# Lower.net
KiCad netlist of a schematic drawn in Altium Designer
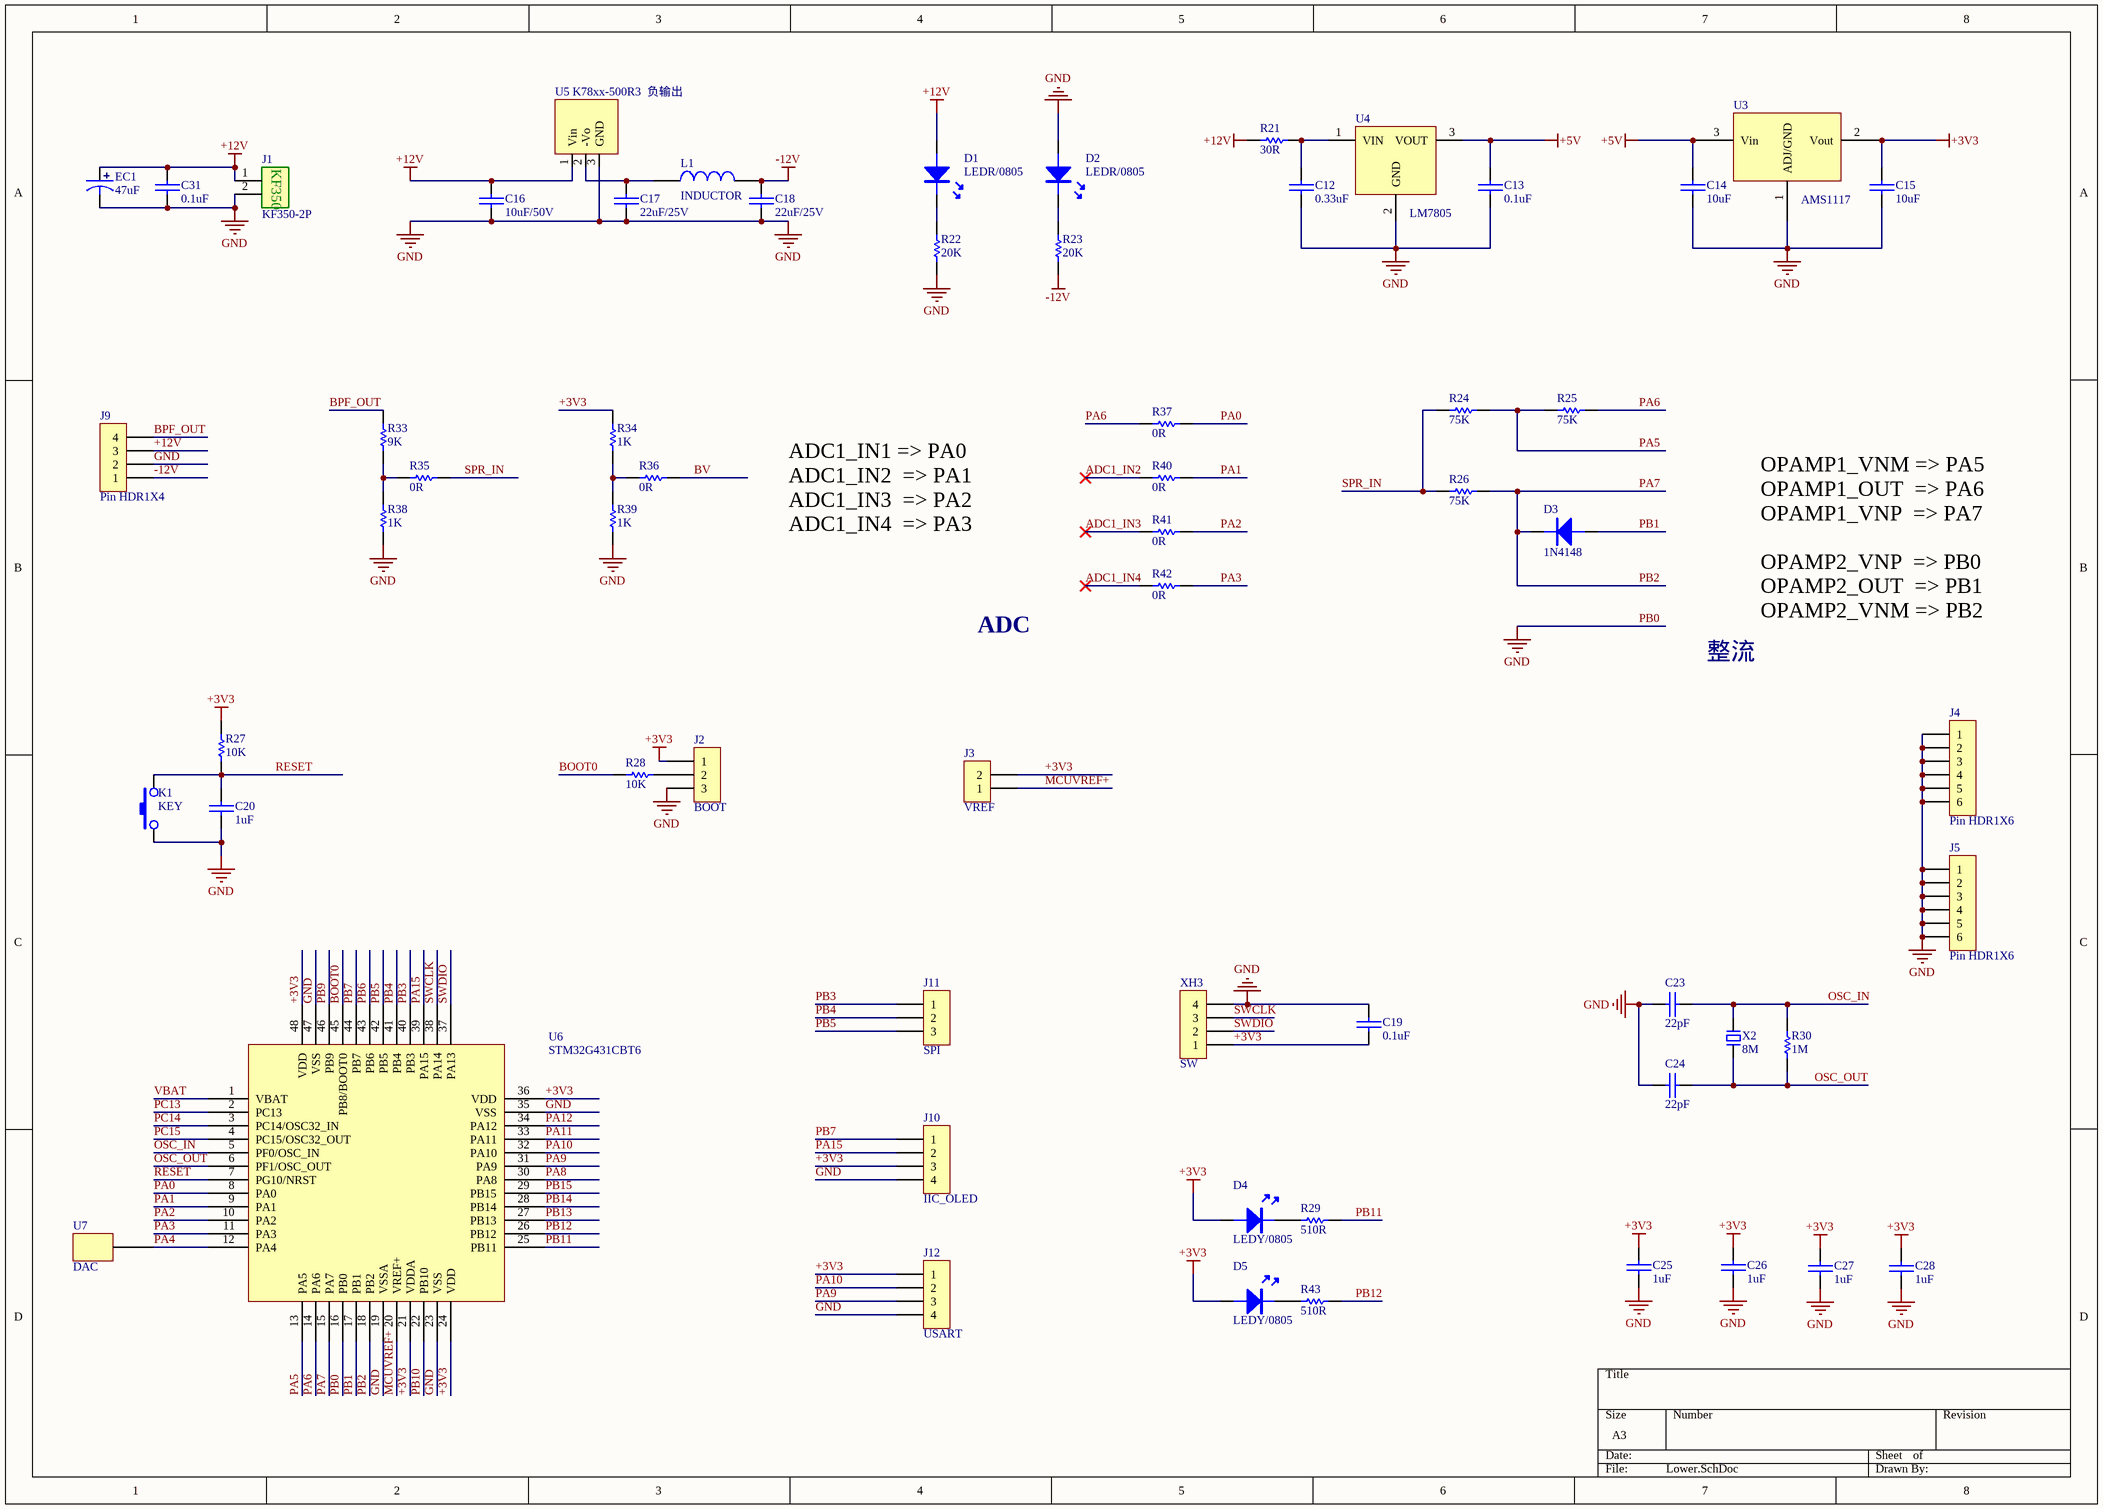
[diagram p0: Lower.SchDoc]

(export (version "E")
  (design (tool "Eeschema 10.0.6"))
  (components
    (comp (ref "C12")
      (value "0.33uF")
      (footprint "0603C")
      (description "无极性电容")
      (libsource (lib "电容") (part "CAP"))
    )
    (comp (ref "C13")
      (value "0.1uF")
      (footprint "0603C")
      (description "无极性电容")
      (libsource (lib "电容") (part "CAP"))
    )
    (comp (ref "C14")
      (value "10uF")
      (footprint "0603C")
      (description "无极性电容")
      (libsource (lib "电容") (part "CAP"))
    )
    (comp (ref "C15")
      (value "10uF")
      (footprint "0603C")
      (description "无极性电容")
      (libsource (lib "电容") (part "CAP"))
    )
    (comp (ref "C16")
      (value "10uF/50V")
      (footprint "0603C")
      (description "无极性电容")
      (libsource (lib "电容") (part "CAP"))
    )
    (comp (ref "C17")
      (value "22uF/25V")
      (footprint "0603C")
      (description "无极性电容")
      (libsource (lib "电容") (part "CAP"))
    )
    (comp (ref "C18")
      (value "22uF/25V")
      (footprint "0603C")
      (description "无极性电容")
      (libsource (lib "电容") (part "CAP"))
    )
    (comp (ref "C19")
      (value "0.1uF")
      (footprint "0603C")
      (description "无极性电容")
      (libsource (lib "电容") (part "CAP"))
    )
    (comp (ref "C20")
      (value "1uF")
      (footprint "0603C")
      (description "无极性电容")
      (libsource (lib "电容") (part "CAP"))
    )
    (comp (ref "C23")
      (value "22pF")
      (footprint "0603C")
      (description "无极性电容")
      (libsource (lib "电容") (part "CAP"))
    )
    (comp (ref "C24")
      (value "22pF")
      (footprint "0603C")
      (description "无极性电容")
      (libsource (lib "电容") (part "CAP"))
    )
    (comp (ref "C25")
      (value "1uF")
      (footprint "0603C")
      (description "无极性电容")
      (libsource (lib "电容") (part "CAP"))
    )
    (comp (ref "C26")
      (value "1uF")
      (footprint "0603C")
      (description "无极性电容")
      (libsource (lib "电容") (part "CAP"))
    )
    (comp (ref "C27")
      (value "1uF")
      (footprint "0603C")
      (description "无极性电容")
      (libsource (lib "电容") (part "CAP"))
    )
    (comp (ref "C28")
      (value "1uF")
      (footprint "0603C")
      (description "无极性电容")
      (libsource (lib "电容") (part "CAP"))
    )
    (comp (ref "C31")
      (value "0.1uF")
      (footprint "0603C")
      (description "无极性电容")
      (libsource (lib "电容") (part "CAP"))
    )
    (comp (ref "D1") (value "LEDR/0805") (footprint "LED-0805R") (libsource (lib "LED") (part "LED")))
    (comp (ref "D2") (value "LEDR/0805") (footprint "LED-0805R") (libsource (lib "LED") (part "LED")))
    (comp (ref "D3")
      (value "1N4148")
      (footprint "SOD-123")
      (description "普通二极管")
      (libsource (lib "二极管") (part "DIODE"))
    )
    (comp (ref "D4") (value "LEDY/0805") (footprint "LED-0805B") (libsource (lib "LED") (part "LED")))
    (comp (ref "D5") (value "LEDY/0805") (footprint "LED-0805G") (libsource (lib "LED") (part "LED")))
    (comp (ref "EC1")
      (value "47uF")
      (footprint "SMD-EC5.0X5.3X5.4")
      (description "贴片电解电容")
      (libsource (lib "电容") (part "SMD_ECAP"))
    )
    (comp (ref "J1") (value "KF350-2P") (footprint "KF350-2P") (libsource (lib "KF350") (part "KF350-2P")))
    (comp (ref "J2")
      (value "BOOT")
      (footprint "Pin HDR1X3/2.54mm-S")
      (libsource (lib "排针") (part "Pin HDR1X3"))
    )
    (comp (ref "J3")
      (value "VREF")
      (footprint "Pin HDR1X2/2.54mm-S")
      (libsource (lib "排针") (part "Pin HDR1X2"))
    )
    (comp (ref "J4")
      (value "Pin HDR1X6")
      (footprint "Pin HDR1X6/2.54mm-S")
      (libsource (lib "排针") (part "Pin HDR1X6"))
    )
    (comp (ref "J5")
      (value "Pin HDR1X6")
      (footprint "Pin HDR1X6/2.54mm-S")
      (libsource (lib "排针") (part "Pin HDR1X6"))
    )
    (comp (ref "J9")
      (value "Pin HDR1X4")
      (footprint "Pin HDR1X4/2.54mm-S")
      (libsource (lib "排针") (part "Pin HDR1X4"))
    )
    (comp (ref "J10")
      (value "IIC_OLED")
      (footprint "Fe-HDR1X4/2.54-S")
      (libsource (lib "排母") (part "Female HDR1X4"))
    )
    (comp (ref "J11")
      (value "SPI")
      (footprint "Pin HDR1X3/2.54mm-S")
      (libsource (lib "排针") (part "Pin HDR1X3"))
    )
    (comp (ref "J12")
      (value "USART")
      (footprint "Fe-HDR1X4/2.54-S")
      (libsource (lib "排母") (part "Female HDR1X4"))
    )
    (comp (ref "K1") (value "KEY") (footprint "SMD-3X6X2.5") (libsource (lib "轻触开关") (part "KEY")))
    (comp (ref "L1") (value "INDUCTOR") (footprint "1210L") (libsource (lib "电感") (part "INDUCTOR")))
    (comp (ref "R21") (value "30R") (footprint "0603R") (libsource (lib "电阻") (part "RES")))
    (comp (ref "R22") (value "20K") (footprint "0603R") (libsource (lib "电阻") (part "RES")))
    (comp (ref "R23") (value "20K") (footprint "0603R") (libsource (lib "电阻") (part "RES")))
    (comp (ref "R24") (value "75K") (footprint "0603R") (libsource (lib "电阻") (part "RES")))
    (comp (ref "R25") (value "75K") (footprint "0603R") (libsource (lib "电阻") (part "RES")))
    (comp (ref "R26") (value "75K") (footprint "0603R") (libsource (lib "电阻") (part "RES")))
    (comp (ref "R27") (value "10K") (footprint "0603R") (libsource (lib "电阻") (part "RES")))
    (comp (ref "R28") (value "10K") (footprint "0603R") (libsource (lib "电阻") (part "RES")))
    (comp (ref "R29") (value "510R") (footprint "0603R") (libsource (lib "电阻") (part "RES")))
    (comp (ref "R30") (value "1M") (footprint "0603R") (libsource (lib "电阻") (part "RES")))
    (comp (ref "R33") (value "9K") (footprint "0603R") (libsource (lib "电阻") (part "RES")))
    (comp (ref "R34") (value "1K") (footprint "0603R") (libsource (lib "电阻") (part "RES")))
    (comp (ref "R35") (value "0R") (footprint "0603R") (libsource (lib "电阻") (part "RES")))
    (comp (ref "R36") (value "0R") (footprint "0603R") (libsource (lib "电阻") (part "RES")))
    (comp (ref "R37") (value "0R") (footprint "0603R") (libsource (lib "电阻") (part "RES")))
    (comp (ref "R38") (value "1K") (footprint "0603R") (libsource (lib "电阻") (part "RES")))
    (comp (ref "R39") (value "1K") (footprint "0603R") (libsource (lib "电阻") (part "RES")))
    (comp (ref "R40") (value "0R") (footprint "0603R") (libsource (lib "电阻") (part "RES")))
    (comp (ref "R41") (value "0R") (footprint "0603R") (libsource (lib "电阻") (part "RES")))
    (comp (ref "R42") (value "0R") (footprint "0603R") (libsource (lib "电阻") (part "RES")))
    (comp (ref "R43") (value "510R") (footprint "0603R") (libsource (lib "电阻") (part "RES")))
    (comp (ref "U3")
      (value "AMS1117")
      (footprint "SOT223")
      (description "三端稳压芯片")
      (libsource (lib "电源芯片") (part "AMS1117"))
    )
    (comp (ref "U4") (value "LM7805") (footprint "TO252") (libsource (lib "电源芯片") (part "LM7805")))
    (comp (ref "U5")
      (value "K78xx-500R3  负输出")
      (footprint "K78xx-500R3 负输出")
      (libsource (lib "传感器") (part "K78xx-500R3  负输出"))
    )
    (comp (ref "U6")
      (value "STM32G431CBT6")
      (footprint "LQFP48 7X7")
      (libsource (lib "STM32系列") (part "STM32G431CBT6"))
    )
    (comp (ref "U7") (value "DAC") (footprint "通孔焊盘") (libsource (lib "排母") (part "过孔焊盘")))
    (comp (ref "X2")
      (value "8M")
      (footprint "OSC HC-49S")
      (description "2脚无源脚晶振")
      (libsource (lib "晶振") (part "XTAL-2P"))
    )
    (comp (ref "XH3") (value "SW") (footprint "XH4/2.54mm/90") (libsource (lib "XH，VH") (part "XH4")))
  )
  (nets
    (net (code "1") (name "+3V3") (class "Default")
      (node (ref "C15") (pin "2") (pinfunction "2_2") (pintype "passive"))
      (node (ref "C19") (pin "1") (pinfunction "1_1") (pintype "passive"))
      (node (ref "C25") (pin "2") (pinfunction "2_2") (pintype "passive"))
      (node (ref "C26") (pin "2") (pinfunction "2_2") (pintype "passive"))
      (node (ref "C27") (pin "2") (pinfunction "2_2") (pintype "passive"))
      (node (ref "C28") (pin "2") (pinfunction "2_2") (pintype "passive"))
      (node (ref "D4") (pin "A") (pinfunction "A_A") (pintype "passive"))
      (node (ref "D5") (pin "A") (pinfunction "A_A") (pintype "passive"))
      (node (ref "J10") (pin "3") (pinfunction "3_3") (pintype "passive"))
      (node (ref "J12") (pin "1") (pinfunction "1_1") (pintype "passive"))
      (node (ref "J2") (pin "1") (pinfunction "1_1") (pintype "passive"))
      (node (ref "J3") (pin "2") (pinfunction "2_2") (pintype "passive"))
      (node (ref "R27") (pin "1") (pinfunction "1_1") (pintype "passive"))
      (node (ref "R34") (pin "2") (pinfunction "2_2") (pintype "passive"))
      (node (ref "U3") (pin "2") (pinfunction "Vout_2") (pintype "passive"))
      (node (ref "U6") (pin "21") (pinfunction "VDDA_21") (pintype "passive"))
      (node (ref "U6") (pin "24") (pinfunction "VDD_24") (pintype "passive"))
      (node (ref "U6") (pin "36") (pinfunction "VDD_36") (pintype "passive"))
      (node (ref "U6") (pin "48") (pinfunction "VDD_48") (pintype "passive"))
      (node (ref "XH3") (pin "1") (pinfunction "1_1") (pintype "passive"))
    )
    (net (code "2") (name "+5V") (class "Default")
      (node (ref "C13") (pin "2") (pinfunction "2_2") (pintype "passive"))
      (node (ref "C14") (pin "2") (pinfunction "2_2") (pintype "passive"))
      (node (ref "U3") (pin "3") (pinfunction "Vin_3") (pintype "passive"))
      (node (ref "U4") (pin "3") (pinfunction "VOUT_3") (pintype "passive"))
    )
    (net (code "3") (name "+12V") (class "Default")
      (node (ref "C16") (pin "2") (pinfunction "2_2") (pintype "passive"))
      (node (ref "C31") (pin "2") (pinfunction "2_2") (pintype "passive"))
      (node (ref "D1") (pin "A") (pinfunction "A_A") (pintype "passive"))
      (node (ref "EC1") (pin "1") (pinfunction "1_1") (pintype "passive"))
      (node (ref "J1") (pin "1") (pinfunction "1_1") (pintype "passive"))
      (node (ref "J9") (pin "3") (pinfunction "3_3") (pintype "passive"))
      (node (ref "R21") (pin "1") (pinfunction "1_1") (pintype "passive"))
      (node (ref "U5") (pin "1") (pinfunction "Vin_1") (pintype "passive"))
    )
    (net (code "4") (name "-12V") (class "Default")
      (node (ref "C18") (pin "2") (pinfunction "2_2") (pintype "passive"))
      (node (ref "J9") (pin "1") (pinfunction "1_1") (pintype "passive"))
      (node (ref "L1") (pin "2") (pinfunction "2_2") (pintype "passive"))
      (node (ref "R23") (pin "2") (pinfunction "2_2") (pintype "passive"))
    )
    (net (code "5") (name "/ADC1_IN2") (class "Default")
      (node (ref "R40") (pin "1") (pinfunction "1_1") (pintype "passive+no_connect"))
    )
    (net (code "6") (name "/ADC1_IN3") (class "Default")
      (node (ref "R41") (pin "1") (pinfunction "1_1") (pintype "passive+no_connect"))
    )
    (net (code "7") (name "/ADC1_IN4") (class "Default")
      (node (ref "R42") (pin "1") (pinfunction "1_1") (pintype "passive+no_connect"))
    )
    (net (code "8") (name "/BOOT0") (class "Default")
      (node (ref "R28") (pin "1") (pinfunction "1_1") (pintype "passive"))
      (node (ref "U6") (pin "45") (pinfunction "PB8/BOOT0_45") (pintype "passive"))
    )
    (net (code "9") (name "/BPF_OUT") (class "Default")
      (node (ref "J9") (pin "4") (pinfunction "4_4") (pintype "passive"))
      (node (ref "R33") (pin "2") (pinfunction "2_2") (pintype "passive"))
    )
    (net (code "10") (name "/BV") (class "Default")
      (node (ref "R36") (pin "1") (pinfunction "1_1") (pintype "passive"))
    )
    (net (code "11") (name "/MCUVREF+") (class "Default")
      (node (ref "J3") (pin "1") (pinfunction "1_1") (pintype "passive"))
      (node (ref "U6") (pin "20") (pinfunction "VREF+_20") (pintype "passive"))
    )
    (net (code "12") (name "/OSC_IN") (class "Default")
      (node (ref "C23") (pin "1") (pinfunction "1_1") (pintype "passive"))
      (node (ref "R30") (pin "2") (pinfunction "2_2") (pintype "passive"))
      (node (ref "U6") (pin "5") (pinfunction "PF0/OSC_IN_5") (pintype "passive"))
      (node (ref "X2") (pin "2") (pinfunction "2_2") (pintype "passive"))
    )
    (net (code "13") (name "/OSC_OUT") (class "Default")
      (node (ref "C24") (pin "1") (pinfunction "1_1") (pintype "passive"))
      (node (ref "R30") (pin "1") (pinfunction "1_1") (pintype "passive"))
      (node (ref "U6") (pin "6") (pinfunction "PF1/OSC_OUT_6") (pintype "passive"))
      (node (ref "X2") (pin "1") (pinfunction "1_1") (pintype "passive"))
    )
    (net (code "14") (name "/PA0") (class "Default")
      (node (ref "R37") (pin "2") (pinfunction "2_2") (pintype "passive"))
      (node (ref "U6") (pin "8") (pinfunction "PA0_8") (pintype "passive"))
    )
    (net (code "15") (name "/PA1") (class "Default")
      (node (ref "R40") (pin "2") (pinfunction "2_2") (pintype "passive"))
      (node (ref "U6") (pin "9") (pinfunction "PA1_9") (pintype "passive"))
    )
    (net (code "16") (name "/PA2") (class "Default")
      (node (ref "R41") (pin "2") (pinfunction "2_2") (pintype "passive"))
      (node (ref "U6") (pin "10") (pinfunction "PA2_10") (pintype "passive"))
    )
    (net (code "17") (name "/PA3") (class "Default")
      (node (ref "R42") (pin "2") (pinfunction "2_2") (pintype "passive"))
      (node (ref "U6") (pin "11") (pinfunction "PA3_11") (pintype "passive"))
    )
    (net (code "18") (name "/PA4") (class "Default")
      (node (ref "U6") (pin "12") (pinfunction "PA4_12") (pintype "passive"))
      (node (ref "U7") (pin "Hole") (pinfunction "Con_Hole") (pintype "passive"))
    )
    (net (code "19") (name "/PA5") (class "Default")
      (node (ref "R24") (pin "2") (pinfunction "2_2") (pintype "passive"))
      (node (ref "R25") (pin "1") (pinfunction "1_1") (pintype "passive"))
      (node (ref "U6") (pin "13") (pinfunction "PA5_13") (pintype "passive"))
    )
    (net (code "20") (name "/PA6") (class "Default")
      (node (ref "R25") (pin "2") (pinfunction "2_2") (pintype "passive"))
      (node (ref "R37") (pin "1") (pinfunction "1_1") (pintype "passive"))
      (node (ref "U6") (pin "14") (pinfunction "PA6_14") (pintype "passive"))
    )
    (net (code "21") (name "/PA7") (class "Default")
      (node (ref "D3") (pin "K") (pinfunction "K_K") (pintype "passive"))
      (node (ref "R26") (pin "2") (pinfunction "2_2") (pintype "passive"))
      (node (ref "U6") (pin "15") (pinfunction "PA7_15") (pintype "passive"))
      (node (ref "U6") (pin "18") (pinfunction "PB2_18") (pintype "passive"))
    )
    (net (code "22") (name "/PA8") (class "Default")
      (node (ref "U6") (pin "30") (pinfunction "PA8_30") (pintype "passive"))
    )
    (net (code "23") (name "/PA9") (class "Default")
      (node (ref "J12") (pin "3") (pinfunction "3_3") (pintype "passive"))
      (node (ref "U6") (pin "31") (pinfunction "PA9_31") (pintype "passive"))
    )
    (net (code "24") (name "/PA10") (class "Default")
      (node (ref "J12") (pin "2") (pinfunction "2_2") (pintype "passive"))
      (node (ref "U6") (pin "32") (pinfunction "PA10_32") (pintype "passive"))
    )
    (net (code "25") (name "/PA11") (class "Default")
      (node (ref "U6") (pin "33") (pinfunction "PA11_33") (pintype "passive"))
    )
    (net (code "26") (name "/PA12") (class "Default")
      (node (ref "U6") (pin "34") (pinfunction "PA12_34") (pintype "passive"))
    )
    (net (code "27") (name "/PA15") (class "Default")
      (node (ref "J10") (pin "2") (pinfunction "2_2") (pintype "passive"))
      (node (ref "U6") (pin "39") (pinfunction "PA15_39") (pintype "passive"))
    )
    (net (code "28") (name "/PB1") (class "Default")
      (node (ref "D3") (pin "A") (pinfunction "A_A") (pintype "passive"))
      (node (ref "U6") (pin "17") (pinfunction "PB1_17") (pintype "passive"))
    )
    (net (code "29") (name "/PB3") (class "Default")
      (node (ref "J11") (pin "1") (pinfunction "1_1") (pintype "passive"))
      (node (ref "U6") (pin "40") (pinfunction "PB3_40") (pintype "passive"))
    )
    (net (code "30") (name "/PB4") (class "Default")
      (node (ref "J11") (pin "2") (pinfunction "2_2") (pintype "passive"))
      (node (ref "U6") (pin "41") (pinfunction "PB4_41") (pintype "passive"))
    )
    (net (code "31") (name "/PB5") (class "Default")
      (node (ref "J11") (pin "3") (pinfunction "3_3") (pintype "passive"))
      (node (ref "U6") (pin "42") (pinfunction "PB5_42") (pintype "passive"))
    )
    (net (code "32") (name "/PB6") (class "Default")
      (node (ref "U6") (pin "43") (pinfunction "PB6_43") (pintype "passive"))
    )
    (net (code "33") (name "/PB7") (class "Default")
      (node (ref "J10") (pin "1") (pinfunction "1_1") (pintype "passive"))
      (node (ref "U6") (pin "44") (pinfunction "PB7_44") (pintype "passive"))
    )
    (net (code "34") (name "/PB9") (class "Default")
      (node (ref "U6") (pin "46") (pinfunction "PB9_46") (pintype "passive"))
    )
    (net (code "35") (name "/PB10") (class "Default")
      (node (ref "U6") (pin "22") (pinfunction "PB10_22") (pintype "passive"))
    )
    (net (code "36") (name "/PB11") (class "Default")
      (node (ref "R29") (pin "2") (pinfunction "2_2") (pintype "passive"))
      (node (ref "U6") (pin "25") (pinfunction "PB11_25") (pintype "passive"))
    )
    (net (code "37") (name "/PB12") (class "Default")
      (node (ref "R43") (pin "2") (pinfunction "2_2") (pintype "passive"))
      (node (ref "U6") (pin "26") (pinfunction "PB12_26") (pintype "passive"))
    )
    (net (code "38") (name "/PB13") (class "Default")
      (node (ref "U6") (pin "27") (pinfunction "PB13_27") (pintype "passive"))
    )
    (net (code "39") (name "/PB14") (class "Default")
      (node (ref "U6") (pin "28") (pinfunction "PB14_28") (pintype "passive"))
    )
    (net (code "40") (name "/PB15") (class "Default")
      (node (ref "U6") (pin "29") (pinfunction "PB15_29") (pintype "passive"))
    )
    (net (code "41") (name "/PC13") (class "Default")
      (node (ref "U6") (pin "2") (pinfunction "PC13_2") (pintype "passive"))
    )
    (net (code "42") (name "/PC14") (class "Default")
      (node (ref "U6") (pin "3") (pinfunction "PC14/OSC32_IN_3") (pintype "passive"))
    )
    (net (code "43") (name "/PC15") (class "Default")
      (node (ref "U6") (pin "4") (pinfunction "PC15/OSC32_OUT_4") (pintype "passive"))
    )
    (net (code "44") (name "/RESET") (class "Default")
      (node (ref "C20") (pin "2") (pinfunction "2_2") (pintype "passive"))
      (node (ref "K1") (pin "3") (pinfunction "3_3") (pintype "passive"))
      (node (ref "R27") (pin "2") (pinfunction "2_2") (pintype "passive"))
      (node (ref "U6") (pin "7") (pinfunction "PG10/NRST_7") (pintype "passive"))
    )
    (net (code "45") (name "/SPR_IN") (class "Default")
      (node (ref "R24") (pin "1") (pinfunction "1_1") (pintype "passive"))
      (node (ref "R26") (pin "1") (pinfunction "1_1") (pintype "passive"))
      (node (ref "R35") (pin "1") (pinfunction "1_1") (pintype "passive"))
    )
    (net (code "46") (name "/SWCLK") (class "Default")
      (node (ref "U6") (pin "38") (pinfunction "PA14_38") (pintype "passive"))
      (node (ref "XH3") (pin "3") (pinfunction "3_3") (pintype "passive"))
    )
    (net (code "47") (name "/SWDIO") (class "Default")
      (node (ref "U6") (pin "37") (pinfunction "PA13_37") (pintype "passive"))
      (node (ref "XH3") (pin "2") (pinfunction "2_2") (pintype "passive"))
    )
    (net (code "48") (name "/VBAT") (class "Default")
      (node (ref "U6") (pin "1") (pinfunction "VBAT_1") (pintype "passive"))
    )
    (net (code "49") (name "GND") (class "Default")
      (node (ref "C12") (pin "1") (pinfunction "1_1") (pintype "passive"))
      (node (ref "C13") (pin "1") (pinfunction "1_1") (pintype "passive"))
      (node (ref "C14") (pin "1") (pinfunction "1_1") (pintype "passive"))
      (node (ref "C15") (pin "1") (pinfunction "1_1") (pintype "passive"))
      (node (ref "C16") (pin "1") (pinfunction "1_1") (pintype "passive"))
      (node (ref "C17") (pin "1") (pinfunction "1_1") (pintype "passive"))
      (node (ref "C18") (pin "1") (pinfunction "1_1") (pintype "passive"))
      (node (ref "C19") (pin "2") (pinfunction "2_2") (pintype "passive"))
      (node (ref "C20") (pin "1") (pinfunction "1_1") (pintype "passive"))
      (node (ref "C23") (pin "2") (pinfunction "2_2") (pintype "passive"))
      (node (ref "C24") (pin "2") (pinfunction "2_2") (pintype "passive"))
      (node (ref "C25") (pin "1") (pinfunction "1_1") (pintype "passive"))
      (node (ref "C26") (pin "1") (pinfunction "1_1") (pintype "passive"))
      (node (ref "C27") (pin "1") (pinfunction "1_1") (pintype "passive"))
      (node (ref "C28") (pin "1") (pinfunction "1_1") (pintype "passive"))
      (node (ref "C31") (pin "1") (pinfunction "1_1") (pintype "passive"))
      (node (ref "D2") (pin "A") (pinfunction "A_A") (pintype "passive"))
      (node (ref "EC1") (pin "2") (pinfunction "2_2") (pintype "passive"))
      (node (ref "J1") (pin "2") (pinfunction "2_2") (pintype "passive"))
      (node (ref "J10") (pin "4") (pinfunction "4_4") (pintype "passive"))
      (node (ref "J12") (pin "4") (pinfunction "4_4") (pintype "passive"))
      (node (ref "J2") (pin "3") (pinfunction "3_3") (pintype "passive"))
      (node (ref "J4") (pin "1") (pinfunction "1_1") (pintype "passive"))
      (node (ref "J4") (pin "2") (pinfunction "2_2") (pintype "passive"))
      (node (ref "J4") (pin "3") (pinfunction "3_3") (pintype "passive"))
      (node (ref "J4") (pin "4") (pinfunction "4_4") (pintype "passive"))
      (node (ref "J4") (pin "5") (pinfunction "5_5") (pintype "passive"))
      (node (ref "J4") (pin "6") (pinfunction "6_6") (pintype "passive"))
      (node (ref "J5") (pin "1") (pinfunction "1_1") (pintype "passive"))
      (node (ref "J5") (pin "2") (pinfunction "2_2") (pintype "passive"))
      (node (ref "J5") (pin "3") (pinfunction "3_3") (pintype "passive"))
      (node (ref "J5") (pin "4") (pinfunction "4_4") (pintype "passive"))
      (node (ref "J5") (pin "5") (pinfunction "5_5") (pintype "passive"))
      (node (ref "J5") (pin "6") (pinfunction "6_6") (pintype "passive"))
      (node (ref "J9") (pin "2") (pinfunction "2_2") (pintype "passive"))
      (node (ref "K1") (pin "1") (pinfunction "1_1") (pintype "passive"))
      (node (ref "R22") (pin "2") (pinfunction "2_2") (pintype "passive"))
      (node (ref "R38") (pin "1") (pinfunction "1_1") (pintype "passive"))
      (node (ref "R39") (pin "1") (pinfunction "1_1") (pintype "passive"))
      (node (ref "U3") (pin "1") (pinfunction "ADJ/GND_1") (pintype "passive"))
      (node (ref "U4") (pin "2") (pinfunction "GND_2") (pintype "passive"))
      (node (ref "U5") (pin "3") (pinfunction "GND_3") (pintype "passive"))
      (node (ref "U6") (pin "16") (pinfunction "PB0_16") (pintype "passive"))
      (node (ref "U6") (pin "19") (pinfunction "VSSA_19") (pintype "passive"))
      (node (ref "U6") (pin "23") (pinfunction "VSS_23") (pintype "passive"))
      (node (ref "U6") (pin "35") (pinfunction "VSS_35") (pintype "passive"))
      (node (ref "U6") (pin "47") (pinfunction "VSS_47") (pintype "passive"))
      (node (ref "XH3") (pin "4") (pinfunction "4_4") (pintype "passive"))
    )
    (net (code "50") (name "Net-(D1-PadK)") (class "Default")
      (node (ref "D1") (pin "K") (pinfunction "K_K") (pintype "passive"))
      (node (ref "R22") (pin "1") (pinfunction "1_1") (pintype "passive"))
    )
    (net (code "51") (name "Net-(D2-PadK)") (class "Default")
      (node (ref "D2") (pin "K") (pinfunction "K_K") (pintype "passive"))
      (node (ref "R23") (pin "1") (pinfunction "1_1") (pintype "passive"))
    )
    (net (code "52") (name "Net-(D4-PadK)") (class "Default")
      (node (ref "D4") (pin "K") (pinfunction "K_K") (pintype "passive"))
      (node (ref "R29") (pin "1") (pinfunction "1_1") (pintype "passive"))
    )
    (net (code "53") (name "Net-(D5-PadK)") (class "Default")
      (node (ref "D5") (pin "K") (pinfunction "K_K") (pintype "passive"))
      (node (ref "R43") (pin "1") (pinfunction "1_1") (pintype "passive"))
    )
    (net (code "54") (name "Net-(J2-Pad2)") (class "Default")
      (node (ref "J2") (pin "2") (pinfunction "2_2") (pintype "passive"))
      (node (ref "R28") (pin "2") (pinfunction "2_2") (pintype "passive"))
    )
    (net (code "55") (name "Net-(R33-Pad1)") (class "Default")
      (node (ref "R33") (pin "1") (pinfunction "1_1") (pintype "passive"))
      (node (ref "R35") (pin "2") (pinfunction "2_2") (pintype "passive"))
      (node (ref "R38") (pin "2") (pinfunction "2_2") (pintype "passive"))
    )
    (net (code "56") (name "Net-(R34-Pad1)") (class "Default")
      (node (ref "R34") (pin "1") (pinfunction "1_1") (pintype "passive"))
      (node (ref "R36") (pin "2") (pinfunction "2_2") (pintype "passive"))
      (node (ref "R39") (pin "2") (pinfunction "2_2") (pintype "passive"))
    )
    (net (code "57") (name "Net-(U4-VIN)") (class "Default")
      (node (ref "C12") (pin "2") (pinfunction "2_2") (pintype "passive"))
      (node (ref "R21") (pin "2") (pinfunction "2_2") (pintype "passive"))
      (node (ref "U4") (pin "1") (pinfunction "VIN_1") (pintype "passive"))
    )
    (net (code "58") (name "Net-(U5--Vo)") (class "Default")
      (node (ref "C17") (pin "2") (pinfunction "2_2") (pintype "passive"))
      (node (ref "L1") (pin "1") (pinfunction "1_1") (pintype "passive"))
      (node (ref "U5") (pin "2") (pinfunction "-Vo_2") (pintype "passive"))
    )
  )
)
